# strum2.net
KiCad netlist of a schematic drawn in EAGLE
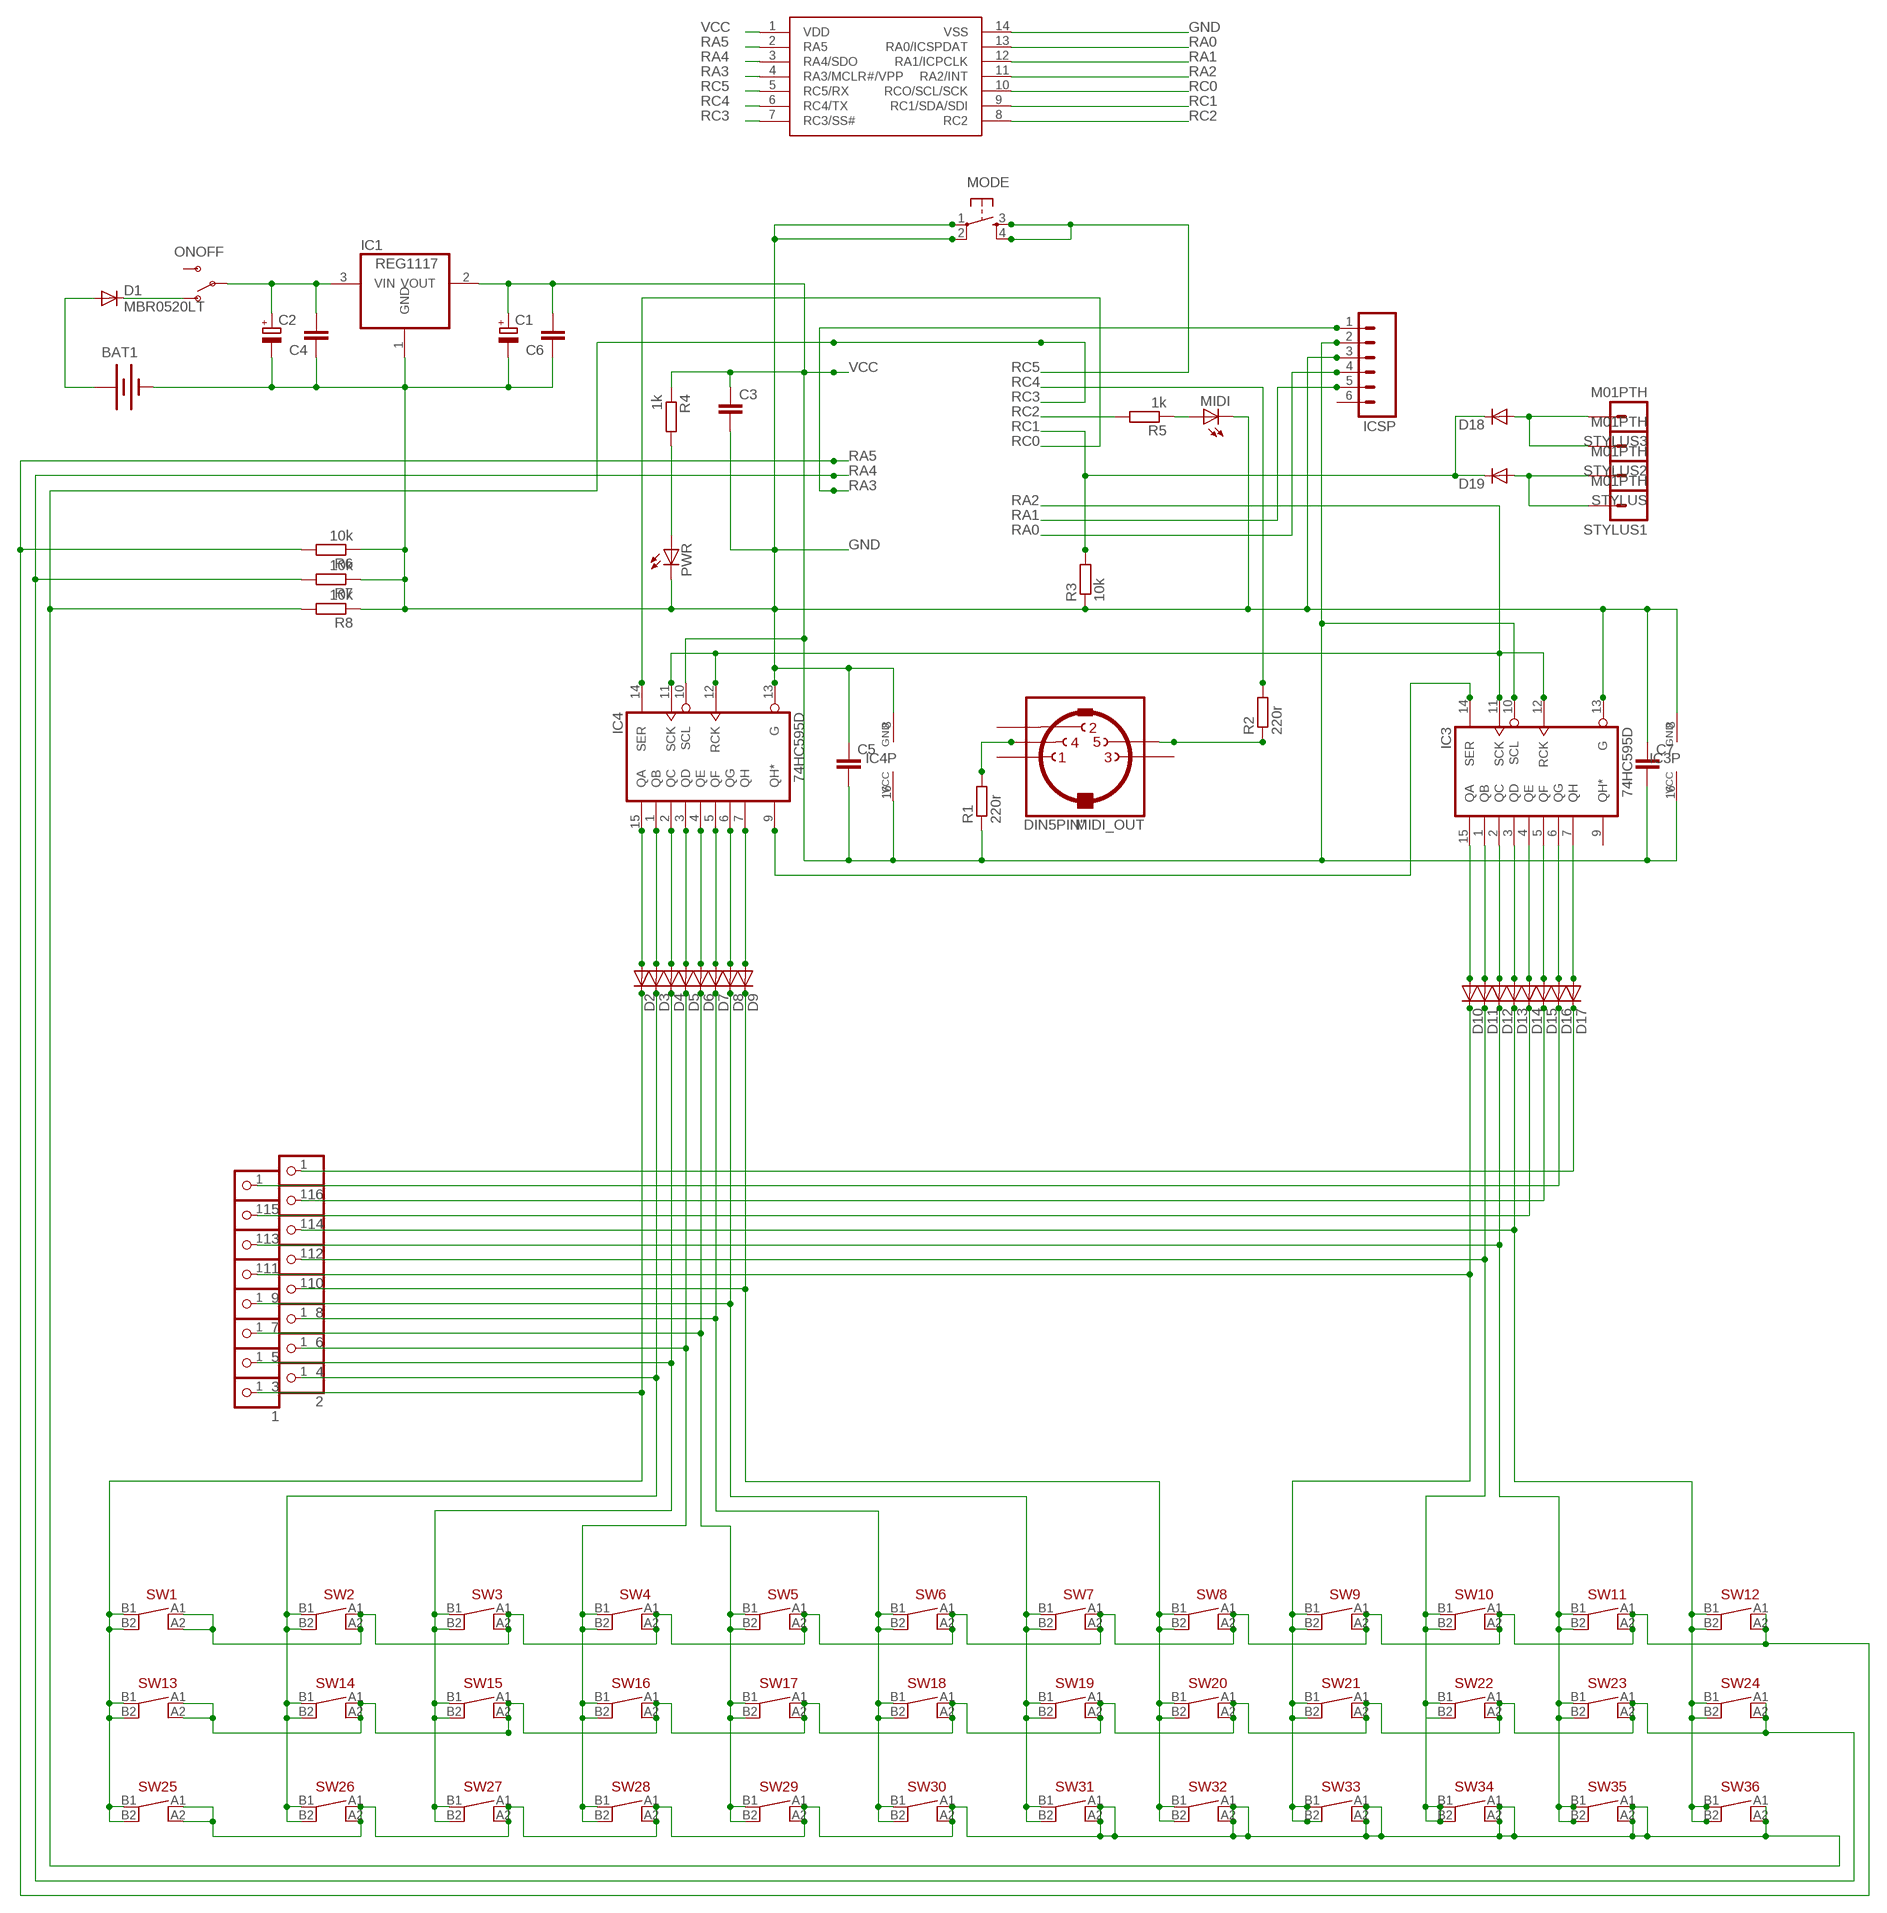
[diagram p0: schematic, sheet 1]

(export (version "E")
  (design (tool "Eeschema 10.0.6"))
  (components
    (comp (ref "1")
      (value "PINHD-1X1")
      (footprint "eagle-import:1X01")
      (libsource (lib "eagle-import") (part "PINHD-1X1"))
    )
    (comp (ref "2")
      (value "PINHD-1X1")
      (footprint "eagle-import:1X01")
      (libsource (lib "eagle-import") (part "PINHD-1X1"))
    )
    (comp (ref "3")
      (value "PINHD-1X1")
      (footprint "eagle-import:1X01")
      (libsource (lib "eagle-import") (part "PINHD-1X1"))
    )
    (comp (ref "4")
      (value "PINHD-1X1")
      (footprint "eagle-import:1X01")
      (libsource (lib "eagle-import") (part "PINHD-1X1"))
    )
    (comp (ref "5")
      (value "PINHD-1X1")
      (footprint "eagle-import:1X01")
      (libsource (lib "eagle-import") (part "PINHD-1X1"))
    )
    (comp (ref "6")
      (value "PINHD-1X1")
      (footprint "eagle-import:1X01")
      (libsource (lib "eagle-import") (part "PINHD-1X1"))
    )
    (comp (ref "7")
      (value "PINHD-1X1")
      (footprint "eagle-import:1X01")
      (libsource (lib "eagle-import") (part "PINHD-1X1"))
    )
    (comp (ref "8")
      (value "PINHD-1X1")
      (footprint "eagle-import:1X01")
      (libsource (lib "eagle-import") (part "PINHD-1X1"))
    )
    (comp (ref "9")
      (value "PINHD-1X1")
      (footprint "eagle-import:1X01")
      (libsource (lib "eagle-import") (part "PINHD-1X1"))
    )
    (comp (ref "10")
      (value "PINHD-1X1")
      (footprint "eagle-import:1X01")
      (libsource (lib "eagle-import") (part "PINHD-1X1"))
    )
    (comp (ref "11")
      (value "PINHD-1X1")
      (footprint "eagle-import:1X01")
      (libsource (lib "eagle-import") (part "PINHD-1X1"))
    )
    (comp (ref "12")
      (value "PINHD-1X1")
      (footprint "eagle-import:1X01")
      (libsource (lib "eagle-import") (part "PINHD-1X1"))
    )
    (comp (ref "13")
      (value "PINHD-1X1")
      (footprint "eagle-import:1X01")
      (libsource (lib "eagle-import") (part "PINHD-1X1"))
    )
    (comp (ref "14")
      (value "PINHD-1X1")
      (footprint "eagle-import:1X01")
      (libsource (lib "eagle-import") (part "PINHD-1X1"))
    )
    (comp (ref "15")
      (value "PINHD-1X1")
      (footprint "eagle-import:1X01")
      (libsource (lib "eagle-import") (part "PINHD-1X1"))
    )
    (comp (ref "16")
      (value "PINHD-1X1")
      (footprint "eagle-import:1X01")
      (libsource (lib "eagle-import") (part "PINHD-1X1"))
    )
    (comp (ref "BAT1")
      (value "BATTERY2HOLES")
      (footprint "eagle-import:PP3_BATTERBOX2")
      (libsource (lib "eagle-import") (part "BATTERY2HOLES"))
    )
    (comp (ref "C1")
      (value "CPOL-EUE2-5")
      (footprint "eagle-import:E2-5")
      (libsource (lib "eagle-import") (part "CPOL-EUE2-5"))
    )
    (comp (ref "C2")
      (value "CPOL-EUE2-5")
      (footprint "eagle-import:E2-5")
      (libsource (lib "eagle-import") (part "CPOL-EUE2-5"))
    )
    (comp (ref "C3")
      (value "C-EUC0805")
      (footprint "eagle-import:C0805")
      (libsource (lib "eagle-import") (part "C-EUC0805"))
    )
    (comp (ref "C4")
      (value "C-EUC0805")
      (footprint "eagle-import:C0805")
      (libsource (lib "eagle-import") (part "C-EUC0805"))
    )
    (comp (ref "C5")
      (value "C-EUC0805")
      (footprint "eagle-import:C0805")
      (libsource (lib "eagle-import") (part "C-EUC0805"))
    )
    (comp (ref "C6")
      (value "C-EUC0805")
      (footprint "eagle-import:C0805")
      (libsource (lib "eagle-import") (part "C-EUC0805"))
    )
    (comp (ref "C7")
      (value "C-EUC0805")
      (footprint "eagle-import:C0805")
      (libsource (lib "eagle-import") (part "C-EUC0805"))
    )
    (comp (ref "D1")
      (value "MBR0520LT")
      (footprint "eagle-import:SOD123")
      (libsource (lib "eagle-import") (part "MBR0520LT"))
    )
    (comp (ref "D2")
      (value "TS4148")
      (footprint "eagle-import:D0805")
      (libsource (lib "eagle-import") (part "TS4148"))
    )
    (comp (ref "D3")
      (value "TS4148")
      (footprint "eagle-import:D0805")
      (libsource (lib "eagle-import") (part "TS4148"))
    )
    (comp (ref "D4")
      (value "TS4148")
      (footprint "eagle-import:D0805")
      (libsource (lib "eagle-import") (part "TS4148"))
    )
    (comp (ref "D5")
      (value "TS4148")
      (footprint "eagle-import:D0805")
      (libsource (lib "eagle-import") (part "TS4148"))
    )
    (comp (ref "D6")
      (value "TS4148")
      (footprint "eagle-import:D0805")
      (libsource (lib "eagle-import") (part "TS4148"))
    )
    (comp (ref "D7")
      (value "TS4148")
      (footprint "eagle-import:D0805")
      (libsource (lib "eagle-import") (part "TS4148"))
    )
    (comp (ref "D8")
      (value "TS4148")
      (footprint "eagle-import:D0805")
      (libsource (lib "eagle-import") (part "TS4148"))
    )
    (comp (ref "D9")
      (value "TS4148")
      (footprint "eagle-import:D0805")
      (libsource (lib "eagle-import") (part "TS4148"))
    )
    (comp (ref "D10")
      (value "TS4148")
      (footprint "eagle-import:D0805")
      (libsource (lib "eagle-import") (part "TS4148"))
    )
    (comp (ref "D11")
      (value "TS4148")
      (footprint "eagle-import:D0805")
      (libsource (lib "eagle-import") (part "TS4148"))
    )
    (comp (ref "D12")
      (value "TS4148")
      (footprint "eagle-import:D0805")
      (libsource (lib "eagle-import") (part "TS4148"))
    )
    (comp (ref "D13")
      (value "TS4148")
      (footprint "eagle-import:D0805")
      (libsource (lib "eagle-import") (part "TS4148"))
    )
    (comp (ref "D14")
      (value "TS4148")
      (footprint "eagle-import:D0805")
      (libsource (lib "eagle-import") (part "TS4148"))
    )
    (comp (ref "D15")
      (value "TS4148")
      (footprint "eagle-import:D0805")
      (libsource (lib "eagle-import") (part "TS4148"))
    )
    (comp (ref "D16")
      (value "TS4148")
      (footprint "eagle-import:D0805")
      (libsource (lib "eagle-import") (part "TS4148"))
    )
    (comp (ref "D17")
      (value "TS4148")
      (footprint "eagle-import:D0805")
      (libsource (lib "eagle-import") (part "TS4148"))
    )
    (comp (ref "D18")
      (value "TS4148")
      (footprint "eagle-import:D0805")
      (libsource (lib "eagle-import") (part "TS4148"))
    )
    (comp (ref "D19")
      (value "TS4148")
      (footprint "eagle-import:D0805")
      (libsource (lib "eagle-import") (part "TS4148"))
    )
    (comp (ref "IC1")
      (value "REG1117")
      (footprint "eagle-import:SOT223")
      (libsource (lib "eagle-import") (part "REG1117"))
    )
    (comp (ref "IC3")
      (value "74HC595D")
      (footprint "eagle-import:SO16")
      (libsource (lib "eagle-import") (part "74595DHC"))
    )
    (comp (ref "IC4")
      (value "74HC595D")
      (footprint "eagle-import:SO16")
      (libsource (lib "eagle-import") (part "74595DHC"))
    )
    (comp (ref "IC5")
      (value "PIC16F1825SO14")
      (footprint "eagle-import:SO14")
      (libsource (lib "eagle-import") (part "PIC16F1825SO14"))
    )
    (comp (ref "ICSP")
      (value "M06SIP")
      (footprint "eagle-import:1X06")
      (libsource (lib "eagle-import") (part "M06SIP"))
    )
    (comp (ref "MIDI")
      (value "LEDCHIPLED_0805")
      (footprint "eagle-import:CHIPLED_0805")
      (libsource (lib "eagle-import") (part "LEDCHIPLED_0805"))
    )
    (comp (ref "MIDI_OUT")
      (value "DIN5PIN\"")
      (footprint "eagle-import:TRUCONN90")
      (libsource (lib "eagle-import") (part "DIN5PIN{dblquote}"))
    )
    (comp (ref "MODE")
      (value "TAC_SWITCHPTH")
      (footprint "eagle-import:TACTILE-PTH")
      (libsource (lib "eagle-import") (part "TAC_SWITCHPTH"))
    )
    (comp (ref "ONOFF")
      (value "SWITCH-SPSTPTH")
      (footprint "eagle-import:SWITCH-SPDT")
      (libsource (lib "eagle-import") (part "SWITCH-SPSTPTH"))
    )
    (comp (ref "PWR")
      (value "LEDCHIPLED_0805")
      (footprint "eagle-import:CHIPLED_0805")
      (libsource (lib "eagle-import") (part "LEDCHIPLED_0805"))
    )
    (comp (ref "R1")
      (value "220r")
      (footprint "eagle-import:R0805")
      (libsource (lib "eagle-import") (part "R-EU_R0805"))
    )
    (comp (ref "R2")
      (value "220r")
      (footprint "eagle-import:R0805")
      (libsource (lib "eagle-import") (part "R-EU_R0805"))
    )
    (comp (ref "R3")
      (value "10k")
      (footprint "eagle-import:R0805")
      (libsource (lib "eagle-import") (part "R-EU_R0805"))
    )
    (comp (ref "R4")
      (value "1k")
      (footprint "eagle-import:R0805")
      (libsource (lib "eagle-import") (part "R-EU_R0805"))
    )
    (comp (ref "R5")
      (value "1k")
      (footprint "eagle-import:R0805")
      (libsource (lib "eagle-import") (part "R-EU_R0805"))
    )
    (comp (ref "R6")
      (value "10k")
      (footprint "eagle-import:R0805")
      (libsource (lib "eagle-import") (part "R-EU_R0805"))
    )
    (comp (ref "R7")
      (value "10k")
      (footprint "eagle-import:R0805")
      (libsource (lib "eagle-import") (part "R-EU_R0805"))
    )
    (comp (ref "R8")
      (value "10k")
      (footprint "eagle-import:R0805")
      (libsource (lib "eagle-import") (part "R-EU_R0805"))
    )
    (comp (ref "STYLUS")
      (value "M01PTH")
      (footprint "eagle-import:1X01")
      (libsource (lib "eagle-import") (part "M01PTH"))
    )
    (comp (ref "STYLUS1")
      (value "M01PTH")
      (footprint "eagle-import:1X01")
      (libsource (lib "eagle-import") (part "M01PTH"))
    )
    (comp (ref "STYLUS2")
      (value "M01PTH")
      (footprint "eagle-import:1X01")
      (libsource (lib "eagle-import") (part "M01PTH"))
    )
    (comp (ref "STYLUS3")
      (value "M01PTH")
      (footprint "eagle-import:1X01")
      (libsource (lib "eagle-import") (part "M01PTH"))
    )
    (comp (ref "SW1")
      (value "12MMTACT_SMT")
      (footprint "eagle-import:12MMTACT_SMT")
      (libsource (lib "eagle-import") (part "12MMTACT_SMT"))
    )
    (comp (ref "SW2")
      (value "12MMTACT_SMT")
      (footprint "eagle-import:12MMTACT_SMT")
      (libsource (lib "eagle-import") (part "12MMTACT_SMT"))
    )
    (comp (ref "SW3")
      (value "12MMTACT_SMT")
      (footprint "eagle-import:12MMTACT_SMT")
      (libsource (lib "eagle-import") (part "12MMTACT_SMT"))
    )
    (comp (ref "SW4")
      (value "12MMTACT_SMT")
      (footprint "eagle-import:12MMTACT_SMT")
      (libsource (lib "eagle-import") (part "12MMTACT_SMT"))
    )
    (comp (ref "SW5")
      (value "12MMTACT_SMT")
      (footprint "eagle-import:12MMTACT_SMT")
      (libsource (lib "eagle-import") (part "12MMTACT_SMT"))
    )
    (comp (ref "SW6")
      (value "12MMTACT_SMT")
      (footprint "eagle-import:12MMTACT_SMT")
      (libsource (lib "eagle-import") (part "12MMTACT_SMT"))
    )
    (comp (ref "SW7")
      (value "12MMTACT_SMT")
      (footprint "eagle-import:12MMTACT_SMT")
      (libsource (lib "eagle-import") (part "12MMTACT_SMT"))
    )
    (comp (ref "SW8")
      (value "12MMTACT_SMT")
      (footprint "eagle-import:12MMTACT_SMT")
      (libsource (lib "eagle-import") (part "12MMTACT_SMT"))
    )
    (comp (ref "SW9")
      (value "12MMTACT_SMT")
      (footprint "eagle-import:12MMTACT_SMT")
      (libsource (lib "eagle-import") (part "12MMTACT_SMT"))
    )
    (comp (ref "SW10")
      (value "12MMTACT_SMT")
      (footprint "eagle-import:12MMTACT_SMT")
      (libsource (lib "eagle-import") (part "12MMTACT_SMT"))
    )
    (comp (ref "SW11")
      (value "12MMTACT_SMT")
      (footprint "eagle-import:12MMTACT_SMT")
      (libsource (lib "eagle-import") (part "12MMTACT_SMT"))
    )
    (comp (ref "SW12")
      (value "12MMTACT_SMT")
      (footprint "eagle-import:12MMTACT_SMT")
      (libsource (lib "eagle-import") (part "12MMTACT_SMT"))
    )
    (comp (ref "SW13")
      (value "12MMTACT_SMT")
      (footprint "eagle-import:12MMTACT_SMT")
      (libsource (lib "eagle-import") (part "12MMTACT_SMT"))
    )
    (comp (ref "SW14")
      (value "12MMTACT_SMT")
      (footprint "eagle-import:12MMTACT_SMT")
      (libsource (lib "eagle-import") (part "12MMTACT_SMT"))
    )
    (comp (ref "SW15")
      (value "12MMTACT_SMT")
      (footprint "eagle-import:12MMTACT_SMT")
      (libsource (lib "eagle-import") (part "12MMTACT_SMT"))
    )
    (comp (ref "SW16")
      (value "12MMTACT_SMT")
      (footprint "eagle-import:12MMTACT_SMT")
      (libsource (lib "eagle-import") (part "12MMTACT_SMT"))
    )
    (comp (ref "SW17")
      (value "12MMTACT_SMT")
      (footprint "eagle-import:12MMTACT_SMT")
      (libsource (lib "eagle-import") (part "12MMTACT_SMT"))
    )
    (comp (ref "SW18")
      (value "12MMTACT_SMT")
      (footprint "eagle-import:12MMTACT_SMT")
      (libsource (lib "eagle-import") (part "12MMTACT_SMT"))
    )
    (comp (ref "SW19")
      (value "12MMTACT_SMT")
      (footprint "eagle-import:12MMTACT_SMT")
      (libsource (lib "eagle-import") (part "12MMTACT_SMT"))
    )
    (comp (ref "SW20")
      (value "12MMTACT_SMT")
      (footprint "eagle-import:12MMTACT_SMT")
      (libsource (lib "eagle-import") (part "12MMTACT_SMT"))
    )
    (comp (ref "SW21")
      (value "12MMTACT_SMT")
      (footprint "eagle-import:12MMTACT_SMT")
      (libsource (lib "eagle-import") (part "12MMTACT_SMT"))
    )
    (comp (ref "SW22")
      (value "12MMTACT_SMT")
      (footprint "eagle-import:12MMTACT_SMT")
      (libsource (lib "eagle-import") (part "12MMTACT_SMT"))
    )
    (comp (ref "SW23")
      (value "12MMTACT_SMT")
      (footprint "eagle-import:12MMTACT_SMT")
      (libsource (lib "eagle-import") (part "12MMTACT_SMT"))
    )
    (comp (ref "SW24")
      (value "12MMTACT_SMT")
      (footprint "eagle-import:12MMTACT_SMT")
      (libsource (lib "eagle-import") (part "12MMTACT_SMT"))
    )
    (comp (ref "SW25")
      (value "12MMTACT_SMT")
      (footprint "eagle-import:12MMTACT_SMT")
      (libsource (lib "eagle-import") (part "12MMTACT_SMT"))
    )
    (comp (ref "SW26")
      (value "12MMTACT_SMT")
      (footprint "eagle-import:12MMTACT_SMT")
      (libsource (lib "eagle-import") (part "12MMTACT_SMT"))
    )
    (comp (ref "SW27")
      (value "12MMTACT_SMT")
      (footprint "eagle-import:12MMTACT_SMT")
      (libsource (lib "eagle-import") (part "12MMTACT_SMT"))
    )
    (comp (ref "SW28")
      (value "12MMTACT_SMT")
      (footprint "eagle-import:12MMTACT_SMT")
      (libsource (lib "eagle-import") (part "12MMTACT_SMT"))
    )
    (comp (ref "SW29")
      (value "12MMTACT_SMT")
      (footprint "eagle-import:12MMTACT_SMT")
      (libsource (lib "eagle-import") (part "12MMTACT_SMT"))
    )
    (comp (ref "SW30")
      (value "12MMTACT_SMT")
      (footprint "eagle-import:12MMTACT_SMT")
      (libsource (lib "eagle-import") (part "12MMTACT_SMT"))
    )
    (comp (ref "SW31")
      (value "12MMTACT_SMT")
      (footprint "eagle-import:12MMTACT_SMT")
      (libsource (lib "eagle-import") (part "12MMTACT_SMT"))
    )
    (comp (ref "SW32")
      (value "12MMTACT_SMT")
      (footprint "eagle-import:12MMTACT_SMT")
      (libsource (lib "eagle-import") (part "12MMTACT_SMT"))
    )
    (comp (ref "SW33")
      (value "12MMTACT_SMT")
      (footprint "eagle-import:12MMTACT_SMT")
      (libsource (lib "eagle-import") (part "12MMTACT_SMT"))
    )
    (comp (ref "SW34")
      (value "12MMTACT_SMT")
      (footprint "eagle-import:12MMTACT_SMT")
      (libsource (lib "eagle-import") (part "12MMTACT_SMT"))
    )
    (comp (ref "SW35")
      (value "12MMTACT_SMT")
      (footprint "eagle-import:12MMTACT_SMT")
      (libsource (lib "eagle-import") (part "12MMTACT_SMT"))
    )
    (comp (ref "SW36")
      (value "12MMTACT_SMT")
      (footprint "eagle-import:12MMTACT_SMT")
      (libsource (lib "eagle-import") (part "12MMTACT_SMT"))
    )
  )
  (nets
    (net (code "1") (name "/GND") (class "Default")
      (node (ref "BAT1") (pin "0V") (pinfunction "-_0V") (pintype "power_in"))
      (node (ref "C1") (pin "-") (pinfunction "-_-") (pintype "passive"))
      (node (ref "C2") (pin "-") (pinfunction "-_-") (pintype "passive"))
      (node (ref "C3") (pin "2") (pinfunction "2_2") (pintype "passive"))
      (node (ref "C4") (pin "1") (pinfunction "1_1") (pintype "passive"))
      (node (ref "C5") (pin "1") (pinfunction "1_1") (pintype "passive"))
      (node (ref "C6") (pin "1") (pinfunction "1_1") (pintype "passive"))
      (node (ref "C7") (pin "1") (pinfunction "1_1") (pintype "passive"))
      (node (ref "IC1") (pin "1") (pinfunction "GND_1") (pintype "power_in"))
      (node (ref "IC3") (pin "13") (pinfunction "G_13") (pintype "input"))
      (node (ref "IC3") (pin "8") (pinfunction "GND_8") (pintype "power_in"))
      (node (ref "IC4") (pin "13") (pinfunction "G_13") (pintype "input"))
      (node (ref "IC4") (pin "8") (pinfunction "GND_8") (pintype "power_in"))
      (node (ref "IC5") (pin "14") (pinfunction "VSS_14") (pintype "power_in"))
      (node (ref "ICSP") (pin "3") (pinfunction "3_3") (pintype "passive"))
      (node (ref "MIDI") (pin "C") (pinfunction "C_C") (pintype "passive"))
      (node (ref "MODE") (pin "1") (pinfunction "1_1") (pintype "passive"))
      (node (ref "MODE") (pin "2") (pinfunction "2_2") (pintype "passive"))
      (node (ref "PWR") (pin "C") (pinfunction "C_C") (pintype "passive"))
      (node (ref "R3") (pin "1") (pinfunction "1_1") (pintype "passive"))
      (node (ref "R6") (pin "1") (pinfunction "1_1") (pintype "passive"))
      (node (ref "R7") (pin "1") (pinfunction "1_1") (pintype "passive"))
      (node (ref "R8") (pin "1") (pinfunction "1_1") (pintype "passive"))
    )
    (net (code "2") (name "/RA0") (class "Default")
      (node (ref "IC5") (pin "13") (pinfunction "RA0/ICSPDAT_13") (pintype "bidirectional"))
      (node (ref "ICSP") (pin "4") (pinfunction "4_4") (pintype "passive"))
    )
    (net (code "3") (name "/RA1") (class "Default")
      (node (ref "IC5") (pin "12") (pinfunction "RA1/ICPCLK_12") (pintype "bidirectional"))
      (node (ref "ICSP") (pin "5") (pinfunction "5_5") (pintype "passive"))
    )
    (net (code "4") (name "/RA2") (class "Default")
      (node (ref "IC3") (pin "11") (pinfunction "SCK_11") (pintype "input"))
      (node (ref "IC3") (pin "12") (pinfunction "RCK_12") (pintype "input"))
      (node (ref "IC4") (pin "11") (pinfunction "SCK_11") (pintype "input"))
      (node (ref "IC4") (pin "12") (pinfunction "RCK_12") (pintype "input"))
      (node (ref "IC5") (pin "11") (pinfunction "RA2/INT_11") (pintype "bidirectional"))
    )
    (net (code "5") (name "/RA3") (class "Default")
      (node (ref "IC5") (pin "4") (pinfunction "RA3/MCLR#/VPP_4") (pintype "input"))
      (node (ref "ICSP") (pin "1") (pinfunction "1_1") (pintype "passive"))
    )
    (net (code "6") (name "/RA4") (class "Default")
      (node (ref "IC5") (pin "3") (pinfunction "RA4/SDO_3") (pintype "bidirectional"))
      (node (ref "R7") (pin "2") (pinfunction "2_2") (pintype "passive"))
      (node (ref "SW13") (pin "A1") (pinfunction "1_A1") (pintype "bidirectional"))
      (node (ref "SW13") (pin "A2") (pinfunction "2_A2") (pintype "bidirectional"))
      (node (ref "SW14") (pin "A1") (pinfunction "1_A1") (pintype "bidirectional"))
      (node (ref "SW14") (pin "A2") (pinfunction "2_A2") (pintype "bidirectional"))
      (node (ref "SW15") (pin "A1") (pinfunction "1_A1") (pintype "bidirectional"))
      (node (ref "SW15") (pin "A2") (pinfunction "2_A2") (pintype "bidirectional"))
      (node (ref "SW16") (pin "A1") (pinfunction "1_A1") (pintype "bidirectional"))
      (node (ref "SW16") (pin "A2") (pinfunction "2_A2") (pintype "bidirectional"))
      (node (ref "SW17") (pin "A1") (pinfunction "1_A1") (pintype "bidirectional"))
      (node (ref "SW17") (pin "A2") (pinfunction "2_A2") (pintype "bidirectional"))
      (node (ref "SW18") (pin "A1") (pinfunction "1_A1") (pintype "bidirectional"))
      (node (ref "SW18") (pin "A2") (pinfunction "2_A2") (pintype "bidirectional"))
      (node (ref "SW19") (pin "A1") (pinfunction "1_A1") (pintype "bidirectional"))
      (node (ref "SW19") (pin "A2") (pinfunction "2_A2") (pintype "bidirectional"))
      (node (ref "SW20") (pin "A1") (pinfunction "1_A1") (pintype "bidirectional"))
      (node (ref "SW20") (pin "A2") (pinfunction "2_A2") (pintype "bidirectional"))
      (node (ref "SW21") (pin "A1") (pinfunction "1_A1") (pintype "bidirectional"))
      (node (ref "SW21") (pin "A2") (pinfunction "2_A2") (pintype "bidirectional"))
      (node (ref "SW22") (pin "A1") (pinfunction "1_A1") (pintype "bidirectional"))
      (node (ref "SW22") (pin "A2") (pinfunction "2_A2") (pintype "bidirectional"))
      (node (ref "SW23") (pin "A1") (pinfunction "1_A1") (pintype "bidirectional"))
      (node (ref "SW23") (pin "A2") (pinfunction "2_A2") (pintype "bidirectional"))
      (node (ref "SW24") (pin "A1") (pinfunction "1_A1") (pintype "bidirectional"))
      (node (ref "SW24") (pin "A2") (pinfunction "2_A2") (pintype "bidirectional"))
    )
    (net (code "7") (name "/RA5") (class "Default")
      (node (ref "IC5") (pin "2") (pinfunction "RA5_2") (pintype "bidirectional"))
      (node (ref "R6") (pin "2") (pinfunction "2_2") (pintype "passive"))
      (node (ref "SW1") (pin "A1") (pinfunction "1_A1") (pintype "bidirectional"))
      (node (ref "SW1") (pin "A2") (pinfunction "2_A2") (pintype "bidirectional"))
      (node (ref "SW10") (pin "A1") (pinfunction "1_A1") (pintype "bidirectional"))
      (node (ref "SW10") (pin "A2") (pinfunction "2_A2") (pintype "bidirectional"))
      (node (ref "SW11") (pin "A1") (pinfunction "1_A1") (pintype "bidirectional"))
      (node (ref "SW11") (pin "A2") (pinfunction "2_A2") (pintype "bidirectional"))
      (node (ref "SW12") (pin "A1") (pinfunction "1_A1") (pintype "bidirectional"))
      (node (ref "SW12") (pin "A2") (pinfunction "2_A2") (pintype "bidirectional"))
      (node (ref "SW2") (pin "A1") (pinfunction "1_A1") (pintype "bidirectional"))
      (node (ref "SW2") (pin "A2") (pinfunction "2_A2") (pintype "bidirectional"))
      (node (ref "SW3") (pin "A1") (pinfunction "1_A1") (pintype "bidirectional"))
      (node (ref "SW3") (pin "A2") (pinfunction "2_A2") (pintype "bidirectional"))
      (node (ref "SW4") (pin "A1") (pinfunction "1_A1") (pintype "bidirectional"))
      (node (ref "SW4") (pin "A2") (pinfunction "2_A2") (pintype "bidirectional"))
      (node (ref "SW5") (pin "A1") (pinfunction "1_A1") (pintype "bidirectional"))
      (node (ref "SW5") (pin "A2") (pinfunction "2_A2") (pintype "bidirectional"))
      (node (ref "SW6") (pin "A1") (pinfunction "1_A1") (pintype "bidirectional"))
      (node (ref "SW6") (pin "A2") (pinfunction "2_A2") (pintype "bidirectional"))
      (node (ref "SW7") (pin "A1") (pinfunction "1_A1") (pintype "bidirectional"))
      (node (ref "SW7") (pin "A2") (pinfunction "2_A2") (pintype "bidirectional"))
      (node (ref "SW8") (pin "A1") (pinfunction "1_A1") (pintype "bidirectional"))
      (node (ref "SW8") (pin "A2") (pinfunction "2_A2") (pintype "bidirectional"))
      (node (ref "SW9") (pin "A1") (pinfunction "1_A1") (pintype "bidirectional"))
      (node (ref "SW9") (pin "A2") (pinfunction "2_A2") (pintype "bidirectional"))
    )
    (net (code "8") (name "/RC0") (class "Default")
      (node (ref "IC4") (pin "14") (pinfunction "SER_14") (pintype "input"))
      (node (ref "IC5") (pin "10") (pinfunction "RCO/SCL/SCK_10") (pintype "bidirectional"))
    )
    (net (code "9") (name "/RC1") (class "Default")
      (node (ref "D18") (pin "K") (pinfunction "C_K") (pintype "passive"))
      (node (ref "D19") (pin "K") (pinfunction "C_K") (pintype "passive"))
      (node (ref "IC5") (pin "9") (pinfunction "RC1/SDA/SDI_9") (pintype "bidirectional"))
      (node (ref "R3") (pin "2") (pinfunction "2_2") (pintype "passive"))
    )
    (net (code "10") (name "/RC2") (class "Default")
      (node (ref "IC5") (pin "8") (pinfunction "RC2_8") (pintype "bidirectional"))
      (node (ref "R5") (pin "2") (pinfunction "2_2") (pintype "passive"))
    )
    (net (code "11") (name "/RC3") (class "Default")
      (node (ref "IC5") (pin "7") (pinfunction "RC3/SS#_7") (pintype "bidirectional"))
      (node (ref "R8") (pin "2") (pinfunction "2_2") (pintype "passive"))
      (node (ref "SW25") (pin "A1") (pinfunction "1_A1") (pintype "bidirectional"))
      (node (ref "SW25") (pin "A2") (pinfunction "2_A2") (pintype "bidirectional"))
      (node (ref "SW26") (pin "A1") (pinfunction "1_A1") (pintype "bidirectional"))
      (node (ref "SW26") (pin "A2") (pinfunction "2_A2") (pintype "bidirectional"))
      (node (ref "SW27") (pin "A1") (pinfunction "1_A1") (pintype "bidirectional"))
      (node (ref "SW27") (pin "A2") (pinfunction "2_A2") (pintype "bidirectional"))
      (node (ref "SW28") (pin "A1") (pinfunction "1_A1") (pintype "bidirectional"))
      (node (ref "SW28") (pin "A2") (pinfunction "2_A2") (pintype "bidirectional"))
      (node (ref "SW29") (pin "A1") (pinfunction "1_A1") (pintype "bidirectional"))
      (node (ref "SW29") (pin "A2") (pinfunction "2_A2") (pintype "bidirectional"))
      (node (ref "SW30") (pin "A1") (pinfunction "1_A1") (pintype "bidirectional"))
      (node (ref "SW30") (pin "A2") (pinfunction "2_A2") (pintype "bidirectional"))
      (node (ref "SW31") (pin "A1") (pinfunction "1_A1") (pintype "bidirectional"))
      (node (ref "SW31") (pin "A2") (pinfunction "2_A2") (pintype "bidirectional"))
      (node (ref "SW32") (pin "A1") (pinfunction "1_A1") (pintype "bidirectional"))
      (node (ref "SW32") (pin "A2") (pinfunction "2_A2") (pintype "bidirectional"))
      (node (ref "SW33") (pin "A1") (pinfunction "1_A1") (pintype "bidirectional"))
      (node (ref "SW33") (pin "A2") (pinfunction "2_A2") (pintype "bidirectional"))
      (node (ref "SW34") (pin "A1") (pinfunction "1_A1") (pintype "bidirectional"))
      (node (ref "SW34") (pin "A2") (pinfunction "2_A2") (pintype "bidirectional"))
      (node (ref "SW35") (pin "A1") (pinfunction "1_A1") (pintype "bidirectional"))
      (node (ref "SW35") (pin "A2") (pinfunction "2_A2") (pintype "bidirectional"))
      (node (ref "SW36") (pin "A1") (pinfunction "1_A1") (pintype "bidirectional"))
      (node (ref "SW36") (pin "A2") (pinfunction "2_A2") (pintype "bidirectional"))
    )
    (net (code "12") (name "/RC4") (class "Default")
      (node (ref "IC5") (pin "6") (pinfunction "RC4/TX_6") (pintype "bidirectional"))
      (node (ref "R2") (pin "2") (pinfunction "2_2") (pintype "passive"))
    )
    (net (code "13") (name "/RC5") (class "Default")
      (node (ref "IC5") (pin "5") (pinfunction "RC5/RX_5") (pintype "bidirectional"))
      (node (ref "MODE") (pin "3") (pinfunction "3_3") (pintype "passive"))
      (node (ref "MODE") (pin "4") (pinfunction "4_4") (pintype "passive"))
    )
    (net (code "14") (name "/VCC") (class "Default")
      (node (ref "C1") (pin "+") (pinfunction "+_+") (pintype "passive"))
      (node (ref "C3") (pin "1") (pinfunction "1_1") (pintype "passive"))
      (node (ref "C5") (pin "2") (pinfunction "2_2") (pintype "passive"))
      (node (ref "C6") (pin "2") (pinfunction "2_2") (pintype "passive"))
      (node (ref "C7") (pin "2") (pinfunction "2_2") (pintype "passive"))
      (node (ref "IC1") (pin "2") (pinfunction "VOUT_2") (pintype "output"))
      (node (ref "IC3") (pin "10") (pinfunction "SCL_10") (pintype "input"))
      (node (ref "IC3") (pin "16") (pinfunction "VCC_16") (pintype "power_in"))
      (node (ref "IC4") (pin "10") (pinfunction "SCL_10") (pintype "input"))
      (node (ref "IC4") (pin "16") (pinfunction "VCC_16") (pintype "power_in"))
      (node (ref "IC5") (pin "1") (pinfunction "VDD_1") (pintype "power_in"))
      (node (ref "ICSP") (pin "2") (pinfunction "2_2") (pintype "passive"))
      (node (ref "R1") (pin "1") (pinfunction "1_1") (pintype "passive"))
      (node (ref "R4") (pin "1") (pinfunction "1_1") (pintype "passive"))
    )
    (net (code "15") (name "Net-(BAT1-+)") (class "Default")
      (node (ref "BAT1") (pin "9V") (pinfunction "+_9V") (pintype "power_in"))
      (node (ref "D1") (pin "A") (pinfunction "A_A") (pintype "passive"))
    )
    (net (code "16") (name "Net-(D2-C)") (class "Default")
      (node (ref "1") (pin "1") (pinfunction "1_1") (pintype "passive"))
      (node (ref "D2") (pin "K") (pinfunction "C_K") (pintype "passive"))
      (node (ref "SW1") (pin "B1") (pinfunction "3_B1") (pintype "bidirectional"))
      (node (ref "SW1") (pin "B2") (pinfunction "4_B2") (pintype "bidirectional"))
      (node (ref "SW13") (pin "B1") (pinfunction "3_B1") (pintype "bidirectional"))
      (node (ref "SW13") (pin "B2") (pinfunction "4_B2") (pintype "bidirectional"))
      (node (ref "SW25") (pin "B1") (pinfunction "3_B1") (pintype "bidirectional"))
      (node (ref "SW25") (pin "B2") (pinfunction "4_B2") (pintype "bidirectional"))
    )
    (net (code "17") (name "Net-(D3-C)") (class "Default")
      (node (ref "2") (pin "1") (pinfunction "1_1") (pintype "passive"))
      (node (ref "D3") (pin "K") (pinfunction "C_K") (pintype "passive"))
      (node (ref "SW14") (pin "B1") (pinfunction "3_B1") (pintype "bidirectional"))
      (node (ref "SW14") (pin "B2") (pinfunction "4_B2") (pintype "bidirectional"))
      (node (ref "SW2") (pin "B1") (pinfunction "3_B1") (pintype "bidirectional"))
      (node (ref "SW2") (pin "B2") (pinfunction "4_B2") (pintype "bidirectional"))
      (node (ref "SW26") (pin "B1") (pinfunction "3_B1") (pintype "bidirectional"))
      (node (ref "SW26") (pin "B2") (pinfunction "4_B2") (pintype "bidirectional"))
    )
    (net (code "18") (name "Net-(D4-C)") (class "Default")
      (node (ref "3") (pin "1") (pinfunction "1_1") (pintype "passive"))
      (node (ref "D4") (pin "K") (pinfunction "C_K") (pintype "passive"))
      (node (ref "SW15") (pin "B1") (pinfunction "3_B1") (pintype "bidirectional"))
      (node (ref "SW15") (pin "B2") (pinfunction "4_B2") (pintype "bidirectional"))
      (node (ref "SW27") (pin "B1") (pinfunction "3_B1") (pintype "bidirectional"))
      (node (ref "SW27") (pin "B2") (pinfunction "4_B2") (pintype "bidirectional"))
      (node (ref "SW3") (pin "B1") (pinfunction "3_B1") (pintype "bidirectional"))
      (node (ref "SW3") (pin "B2") (pinfunction "4_B2") (pintype "bidirectional"))
    )
    (net (code "19") (name "Net-(D5-C)") (class "Default")
      (node (ref "4") (pin "1") (pinfunction "1_1") (pintype "passive"))
      (node (ref "D5") (pin "K") (pinfunction "C_K") (pintype "passive"))
      (node (ref "SW16") (pin "B1") (pinfunction "3_B1") (pintype "bidirectional"))
      (node (ref "SW16") (pin "B2") (pinfunction "4_B2") (pintype "bidirectional"))
      (node (ref "SW28") (pin "B1") (pinfunction "3_B1") (pintype "bidirectional"))
      (node (ref "SW28") (pin "B2") (pinfunction "4_B2") (pintype "bidirectional"))
      (node (ref "SW4") (pin "B1") (pinfunction "3_B1") (pintype "bidirectional"))
      (node (ref "SW4") (pin "B2") (pinfunction "4_B2") (pintype "bidirectional"))
    )
    (net (code "20") (name "Net-(D6-C)") (class "Default")
      (node (ref "5") (pin "1") (pinfunction "1_1") (pintype "passive"))
      (node (ref "D6") (pin "K") (pinfunction "C_K") (pintype "passive"))
      (node (ref "SW17") (pin "B1") (pinfunction "3_B1") (pintype "bidirectional"))
      (node (ref "SW17") (pin "B2") (pinfunction "4_B2") (pintype "bidirectional"))
      (node (ref "SW29") (pin "B1") (pinfunction "3_B1") (pintype "bidirectional"))
      (node (ref "SW29") (pin "B2") (pinfunction "4_B2") (pintype "bidirectional"))
      (node (ref "SW5") (pin "B1") (pinfunction "3_B1") (pintype "bidirectional"))
      (node (ref "SW5") (pin "B2") (pinfunction "4_B2") (pintype "bidirectional"))
    )
    (net (code "21") (name "Net-(D7-C)") (class "Default")
      (node (ref "6") (pin "1") (pinfunction "1_1") (pintype "passive"))
      (node (ref "D7") (pin "K") (pinfunction "C_K") (pintype "passive"))
      (node (ref "SW18") (pin "B1") (pinfunction "3_B1") (pintype "bidirectional"))
      (node (ref "SW18") (pin "B2") (pinfunction "4_B2") (pintype "bidirectional"))
      (node (ref "SW30") (pin "B1") (pinfunction "3_B1") (pintype "bidirectional"))
      (node (ref "SW30") (pin "B2") (pinfunction "4_B2") (pintype "bidirectional"))
      (node (ref "SW6") (pin "B1") (pinfunction "3_B1") (pintype "bidirectional"))
      (node (ref "SW6") (pin "B2") (pinfunction "4_B2") (pintype "bidirectional"))
    )
    (net (code "22") (name "Net-(D8-C)") (class "Default")
      (node (ref "7") (pin "1") (pinfunction "1_1") (pintype "passive"))
      (node (ref "D8") (pin "K") (pinfunction "C_K") (pintype "passive"))
      (node (ref "SW19") (pin "B1") (pinfunction "3_B1") (pintype "bidirectional"))
      (node (ref "SW19") (pin "B2") (pinfunction "4_B2") (pintype "bidirectional"))
      (node (ref "SW31") (pin "B1") (pinfunction "3_B1") (pintype "bidirectional"))
      (node (ref "SW31") (pin "B2") (pinfunction "4_B2") (pintype "bidirectional"))
      (node (ref "SW7") (pin "B1") (pinfunction "3_B1") (pintype "bidirectional"))
      (node (ref "SW7") (pin "B2") (pinfunction "4_B2") (pintype "bidirectional"))
    )
    (net (code "23") (name "Net-(D9-C)") (class "Default")
      (node (ref "8") (pin "1") (pinfunction "1_1") (pintype "passive"))
      (node (ref "D9") (pin "K") (pinfunction "C_K") (pintype "passive"))
      (node (ref "SW20") (pin "B1") (pinfunction "3_B1") (pintype "bidirectional"))
      (node (ref "SW20") (pin "B2") (pinfunction "4_B2") (pintype "bidirectional"))
      (node (ref "SW32") (pin "B1") (pinfunction "3_B1") (pintype "bidirectional"))
      (node (ref "SW32") (pin "B2") (pinfunction "4_B2") (pintype "bidirectional"))
      (node (ref "SW8") (pin "B1") (pinfunction "3_B1") (pintype "bidirectional"))
      (node (ref "SW8") (pin "B2") (pinfunction "4_B2") (pintype "bidirectional"))
    )
    (net (code "24") (name "Net-(D10-C)") (class "Default")
      (node (ref "9") (pin "1") (pinfunction "1_1") (pintype "passive"))
      (node (ref "D10") (pin "K") (pinfunction "C_K") (pintype "passive"))
      (node (ref "SW21") (pin "B1") (pinfunction "3_B1") (pintype "bidirectional"))
      (node (ref "SW21") (pin "B2") (pinfunction "4_B2") (pintype "bidirectional"))
      (node (ref "SW33") (pin "B1") (pinfunction "3_B1") (pintype "bidirectional"))
      (node (ref "SW33") (pin "B2") (pinfunction "4_B2") (pintype "bidirectional"))
      (node (ref "SW9") (pin "B1") (pinfunction "3_B1") (pintype "bidirectional"))
      (node (ref "SW9") (pin "B2") (pinfunction "4_B2") (pintype "bidirectional"))
    )
    (net (code "25") (name "Net-(D11-C)") (class "Default")
      (node (ref "10") (pin "1") (pinfunction "1_1") (pintype "passive"))
      (node (ref "D11") (pin "K") (pinfunction "C_K") (pintype "passive"))
      (node (ref "SW10") (pin "B1") (pinfunction "3_B1") (pintype "bidirectional"))
      (node (ref "SW10") (pin "B2") (pinfunction "4_B2") (pintype "bidirectional"))
      (node (ref "SW22") (pin "B1") (pinfunction "3_B1") (pintype "bidirectional"))
      (node (ref "SW22") (pin "B2") (pinfunction "4_B2") (pintype "bidirectional"))
      (node (ref "SW34") (pin "B1") (pinfunction "3_B1") (pintype "bidirectional"))
      (node (ref "SW34") (pin "B2") (pinfunction "4_B2") (pintype "bidirectional"))
    )
    (net (code "26") (name "Net-(D12-C)") (class "Default")
      (node (ref "11") (pin "1") (pinfunction "1_1") (pintype "passive"))
      (node (ref "D12") (pin "K") (pinfunction "C_K") (pintype "passive"))
      (node (ref "SW11") (pin "B1") (pinfunction "3_B1") (pintype "bidirectional"))
      (node (ref "SW11") (pin "B2") (pinfunction "4_B2") (pintype "bidirectional"))
      (node (ref "SW23") (pin "B1") (pinfunction "3_B1") (pintype "bidirectional"))
      (node (ref "SW23") (pin "B2") (pinfunction "4_B2") (pintype "bidirectional"))
      (node (ref "SW35") (pin "B1") (pinfunction "3_B1") (pintype "bidirectional"))
      (node (ref "SW35") (pin "B2") (pinfunction "4_B2") (pintype "bidirectional"))
    )
    (net (code "27") (name "Net-(D13-C)") (class "Default")
      (node (ref "12") (pin "1") (pinfunction "1_1") (pintype "passive"))
      (node (ref "D13") (pin "K") (pinfunction "C_K") (pintype "passive"))
      (node (ref "SW12") (pin "B1") (pinfunction "3_B1") (pintype "bidirectional"))
      (node (ref "SW12") (pin "B2") (pinfunction "4_B2") (pintype "bidirectional"))
      (node (ref "SW24") (pin "B1") (pinfunction "3_B1") (pintype "bidirectional"))
      (node (ref "SW24") (pin "B2") (pinfunction "4_B2") (pintype "bidirectional"))
      (node (ref "SW36") (pin "B1") (pinfunction "3_B1") (pintype "bidirectional"))
      (node (ref "SW36") (pin "B2") (pinfunction "4_B2") (pintype "bidirectional"))
    )
    (net (code "28") (name "Net-(D14-C)") (class "Default")
      (node (ref "13") (pin "1") (pinfunction "1_1") (pintype "passive"))
      (node (ref "D14") (pin "K") (pinfunction "C_K") (pintype "passive"))
    )
    (net (code "29") (name "Net-(D15-C)") (class "Default")
      (node (ref "14") (pin "1") (pinfunction "1_1") (pintype "passive"))
      (node (ref "D15") (pin "K") (pinfunction "C_K") (pintype "passive"))
    )
    (net (code "30") (name "Net-(D16-C)") (class "Default")
      (node (ref "15") (pin "1") (pinfunction "1_1") (pintype "passive"))
      (node (ref "D16") (pin "K") (pinfunction "C_K") (pintype "passive"))
    )
    (net (code "31") (name "Net-(D17-C)") (class "Default")
      (node (ref "16") (pin "1") (pinfunction "1_1") (pintype "passive"))
      (node (ref "D17") (pin "K") (pinfunction "C_K") (pintype "passive"))
    )
    (net (code "32") (name "Net-(D18-PadA)") (class "Default")
      (node (ref "D18") (pin "A") (pinfunction "A_A") (pintype "passive"))
      (node (ref "STYLUS2") (pin "1") (pinfunction "1_1") (pintype "passive"))
      (node (ref "STYLUS3") (pin "1") (pinfunction "1_1") (pintype "passive"))
    )
    (net (code "33") (name "Net-(D19-PadA)") (class "Default")
      (node (ref "D19") (pin "A") (pinfunction "A_A") (pintype "passive"))
      (node (ref "STYLUS") (pin "1") (pinfunction "1_1") (pintype "passive"))
      (node (ref "STYLUS1") (pin "1") (pinfunction "1_1") (pintype "passive"))
    )
    (net (code "34") (name "Net-(IC1-VIN)") (class "Default")
      (node (ref "C2") (pin "+") (pinfunction "+_+") (pintype "passive"))
      (node (ref "C4") (pin "2") (pinfunction "2_2") (pintype "passive"))
      (node (ref "IC1") (pin "3") (pinfunction "VIN_3") (pintype "input"))
      (node (ref "ONOFF") (pin "2") (pinfunction "P_2") (pintype "passive"))
    )
    (net (code "35") (name "Net-(IC3A-QA)") (class "Default")
      (node (ref "D10") (pin "A") (pinfunction "A_A") (pintype "passive"))
      (node (ref "IC3") (pin "15") (pinfunction "QA_15") (pintype "tri_state"))
    )
    (net (code "36") (name "Net-(IC3A-QB)") (class "Default")
      (node (ref "D11") (pin "A") (pinfunction "A_A") (pintype "passive"))
      (node (ref "IC3") (pin "1") (pinfunction "QB_1") (pintype "tri_state"))
    )
    (net (code "37") (name "Net-(IC3A-QC)") (class "Default")
      (node (ref "D12") (pin "A") (pinfunction "A_A") (pintype "passive"))
      (node (ref "IC3") (pin "2") (pinfunction "QC_2") (pintype "tri_state"))
    )
    (net (code "38") (name "Net-(IC3A-QD)") (class "Default")
      (node (ref "D13") (pin "A") (pinfunction "A_A") (pintype "passive"))
      (node (ref "IC3") (pin "3") (pinfunction "QD_3") (pintype "tri_state"))
    )
    (net (code "39") (name "Net-(IC3A-QE)") (class "Default")
      (node (ref "D14") (pin "A") (pinfunction "A_A") (pintype "passive"))
      (node (ref "IC3") (pin "4") (pinfunction "QE_4") (pintype "tri_state"))
    )
    (net (code "40") (name "Net-(IC3A-QF)") (class "Default")
      (node (ref "D15") (pin "A") (pinfunction "A_A") (pintype "passive"))
      (node (ref "IC3") (pin "5") (pinfunction "QF_5") (pintype "tri_state"))
    )
    (net (code "41") (name "Net-(IC3A-QG)") (class "Default")
      (node (ref "D16") (pin "A") (pinfunction "A_A") (pintype "passive"))
      (node (ref "IC3") (pin "6") (pinfunction "QG_6") (pintype "tri_state"))
    )
    (net (code "42") (name "Net-(IC3A-QH)") (class "Default")
      (node (ref "D17") (pin "A") (pinfunction "A_A") (pintype "passive"))
      (node (ref "IC3") (pin "7") (pinfunction "QH_7") (pintype "tri_state"))
    )
    (net (code "43") (name "Net-(IC3A-SER)") (class "Default")
      (node (ref "IC3") (pin "14") (pinfunction "SER_14") (pintype "input"))
      (node (ref "IC4") (pin "9") (pinfunction "QH*_9") (pintype "tri_state"))
    )
    (net (code "44") (name "Net-(IC4A-QA)") (class "Default")
      (node (ref "D2") (pin "A") (pinfunction "A_A") (pintype "passive"))
      (node (ref "IC4") (pin "15") (pinfunction "QA_15") (pintype "tri_state"))
    )
    (net (code "45") (name "Net-(IC4A-QB)") (class "Default")
      (node (ref "D3") (pin "A") (pinfunction "A_A") (pintype "passive"))
      (node (ref "IC4") (pin "1") (pinfunction "QB_1") (pintype "tri_state"))
    )
    (net (code "46") (name "Net-(IC4A-QC)") (class "Default")
      (node (ref "D4") (pin "A") (pinfunction "A_A") (pintype "passive"))
      (node (ref "IC4") (pin "2") (pinfunction "QC_2") (pintype "tri_state"))
    )
    (net (code "47") (name "Net-(IC4A-QD)") (class "Default")
      (node (ref "D5") (pin "A") (pinfunction "A_A") (pintype "passive"))
      (node (ref "IC4") (pin "3") (pinfunction "QD_3") (pintype "tri_state"))
    )
    (net (code "48") (name "Net-(IC4A-QE)") (class "Default")
      (node (ref "D6") (pin "A") (pinfunction "A_A") (pintype "passive"))
      (node (ref "IC4") (pin "4") (pinfunction "QE_4") (pintype "tri_state"))
    )
    (net (code "49") (name "Net-(IC4A-QF)") (class "Default")
      (node (ref "D7") (pin "A") (pinfunction "A_A") (pintype "passive"))
      (node (ref "IC4") (pin "5") (pinfunction "QF_5") (pintype "tri_state"))
    )
    (net (code "50") (name "Net-(IC4A-QG)") (class "Default")
      (node (ref "D8") (pin "A") (pinfunction "A_A") (pintype "passive"))
      (node (ref "IC4") (pin "6") (pinfunction "QG_6") (pintype "tri_state"))
    )
    (net (code "51") (name "Net-(IC4A-QH)") (class "Default")
      (node (ref "D9") (pin "A") (pinfunction "A_A") (pintype "passive"))
      (node (ref "IC4") (pin "7") (pinfunction "QH_7") (pintype "tri_state"))
    )
    (net (code "52") (name "Net-(MIDI-PadA)") (class "Default")
      (node (ref "MIDI") (pin "A") (pinfunction "A_A") (pintype "passive"))
      (node (ref "R5") (pin "1") (pinfunction "1_1") (pintype "passive"))
    )
    (net (code "53") (name "Net-(MIDI_OUT-Pad4)") (class "Default")
      (node (ref "MIDI_OUT") (pin "4") (pinfunction "4_4") (pintype "passive"))
      (node (ref "R1") (pin "2") (pinfunction "2_2") (pintype "passive"))
    )
    (net (code "54") (name "Net-(MIDI_OUT-Pad5)") (class "Default")
      (node (ref "MIDI_OUT") (pin "5") (pinfunction "5_5") (pintype "passive"))
      (node (ref "R2") (pin "1") (pinfunction "1_1") (pintype "passive"))
    )
    (net (code "55") (name "Net-(ONOFF-O)") (class "Default")
      (node (ref "D1") (pin "C") (pinfunction "C_C") (pintype "passive"))
      (node (ref "ONOFF") (pin "1") (pinfunction "O_1") (pintype "passive"))
    )
    (net (code "56") (name "Net-(PWR-PadA)") (class "Default")
      (node (ref "PWR") (pin "A") (pinfunction "A_A") (pintype "passive"))
      (node (ref "R4") (pin "2") (pinfunction "2_2") (pintype "passive"))
    )
    (net (code "57") (name "unconnected-(IC3A-QH*-Pad9)") (class "Default")
      (node (ref "IC3") (pin "9") (pinfunction "QH*_9") (pintype "tri_state"))
    )
    (net (code "58") (name "unconnected-(ICSP-Pad6)") (class "Default")
      (node (ref "ICSP") (pin "6") (pinfunction "6_6") (pintype "passive"))
    )
    (net (code "59") (name "unconnected-(MIDI_OUT-Pad1)") (class "Default")
      (node (ref "MIDI_OUT") (pin "1") (pinfunction "1_1") (pintype "passive"))
    )
    (net (code "60") (name "unconnected-(MIDI_OUT-Pad2)") (class "Default")
      (node (ref "MIDI_OUT") (pin "2") (pinfunction "2_2") (pintype "passive"))
    )
    (net (code "61") (name "unconnected-(MIDI_OUT-Pad3)") (class "Default")
      (node (ref "MIDI_OUT") (pin "3") (pinfunction "3_3") (pintype "passive"))
    )
    (net (code "62") (name "unconnected-(ONOFF-S-Pad3)") (class "Default")
      (node (ref "ONOFF") (pin "3") (pinfunction "S_3") (pintype "passive"))
    )
  )
)
